# untitled.net
KiCad netlist of a schematic drawn in EAGLE
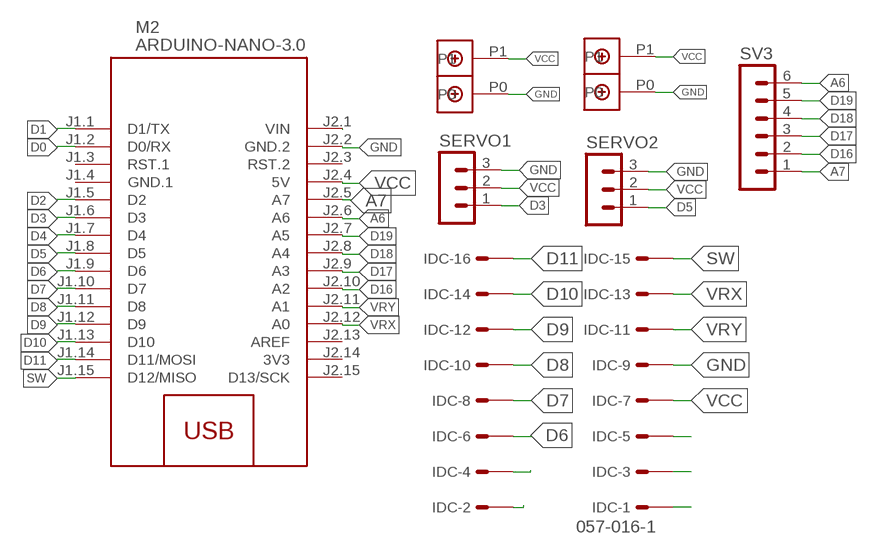
[diagram p0: schematic, sheet 1]

(export (version "E")
  (design (tool "Eeschema 10.0.6"))
  (components
    (comp (ref "IDC")
      (value "057-016-1")
      (footprint "eagle-import:057-016-1")
      (libsource (lib "eagle-import") (part "057-016-1"))
    )
    (comp (ref "M2")
      (value "ARDUINO-NANO-3.0")
      (footprint "eagle-import:ARDUINO-NANO-3.0")
      (libsource (lib "eagle-import") (part "ARDUINO-NANO-3.0"))
    )
    (comp (ref "SERVO1")
      (value "MA03-1")
      (footprint "eagle-import:MA03-1")
      (libsource (lib "eagle-import") (part "MA03-1"))
    )
    (comp (ref "SERVO2")
      (value "MA03-1")
      (footprint "eagle-import:MA03-1")
      (libsource (lib "eagle-import") (part "MA03-1"))
    )
    (comp (ref "SV3")
      (value "MA06-1")
      (footprint "eagle-import:MA06-1")
      (libsource (lib "eagle-import") (part "MA06-1"))
    )
    (comp (ref "U$1")
      (value "DBCONN-1X2")
      (footprint "eagle-import:DBCONN-1X2")
      (libsource (lib "eagle-import") (part "DBCONN-1X2"))
    )
    (comp (ref "U$2")
      (value "DBCONN-1X2")
      (footprint "eagle-import:DBCONN-1X2")
      (libsource (lib "eagle-import") (part "DBCONN-1X2"))
    )
  )
  (nets
    (net (code "1") (name "/3V3") (class "Default")
      (node (ref "M2") (pin "J2.14") (pinfunction "3V3_J2.14") (pintype "power_in"))
    )
    (net (code "2") (name "/D") (class "Default")
      (node (ref "IDC") (pin "2") (pinfunction "S_2") (pintype "passive"))
      (node (ref "IDC") (pin "4") (pinfunction "S_4") (pintype "passive"))
    )
    (net (code "3") (name "/GND.1") (class "Default")
      (node (ref "M2") (pin "J1.4") (pinfunction "GND.1_J1.4") (pintype "power_in"))
    )
    (net (code "4") (name "A6") (class "Default")
      (node (ref "M2") (pin "J2.6") (pinfunction "A6_J2.6") (pintype "bidirectional"))
      (node (ref "SV3") (pin "6") (pinfunction "6_6") (pintype "passive"))
    )
    (net (code "5") (name "A7") (class "Default")
      (node (ref "M2") (pin "J2.5") (pinfunction "A7_J2.5") (pintype "bidirectional"))
      (node (ref "SV3") (pin "1") (pinfunction "1_1") (pintype "passive"))
    )
    (net (code "6") (name "D0") (class "Default")
      (node (ref "M2") (pin "J1.2") (pinfunction "D0/RX_J1.2") (pintype "bidirectional"))
    )
    (net (code "7") (name "D1") (class "Default")
      (node (ref "M2") (pin "J1.1") (pinfunction "D1/TX_J1.1") (pintype "bidirectional"))
    )
    (net (code "8") (name "D2") (class "Default")
      (node (ref "M2") (pin "J1.5") (pinfunction "D2_J1.5") (pintype "bidirectional"))
    )
    (net (code "9") (name "D3") (class "Default")
      (node (ref "M2") (pin "J1.6") (pinfunction "D3_J1.6") (pintype "bidirectional"))
      (node (ref "SERVO1") (pin "1") (pinfunction "1_1") (pintype "passive"))
    )
    (net (code "10") (name "D4") (class "Default")
      (node (ref "M2") (pin "J1.7") (pinfunction "D4_J1.7") (pintype "bidirectional"))
    )
    (net (code "11") (name "D5") (class "Default")
      (node (ref "M2") (pin "J1.8") (pinfunction "D5_J1.8") (pintype "bidirectional"))
      (node (ref "SERVO2") (pin "1") (pinfunction "1_1") (pintype "passive"))
    )
    (net (code "12") (name "D6") (class "Default")
      (node (ref "IDC") (pin "6") (pinfunction "S_6") (pintype "passive"))
      (node (ref "M2") (pin "J1.9") (pinfunction "D6_J1.9") (pintype "bidirectional"))
    )
    (net (code "13") (name "D7") (class "Default")
      (node (ref "IDC") (pin "8") (pinfunction "S_8") (pintype "passive"))
      (node (ref "M2") (pin "J1.10") (pinfunction "D7_J1.10") (pintype "bidirectional"))
    )
    (net (code "14") (name "D8") (class "Default")
      (node (ref "IDC") (pin "10") (pinfunction "S_10") (pintype "passive"))
      (node (ref "M2") (pin "J1.11") (pinfunction "D8_J1.11") (pintype "bidirectional"))
    )
    (net (code "15") (name "D9") (class "Default")
      (node (ref "IDC") (pin "12") (pinfunction "S_12") (pintype "passive"))
      (node (ref "M2") (pin "J1.12") (pinfunction "D9_J1.12") (pintype "bidirectional"))
    )
    (net (code "16") (name "D10") (class "Default")
      (node (ref "IDC") (pin "14") (pinfunction "S_14") (pintype "passive"))
      (node (ref "M2") (pin "J1.13") (pinfunction "D10_J1.13") (pintype "bidirectional"))
    )
    (net (code "17") (name "D11") (class "Default")
      (node (ref "IDC") (pin "16") (pinfunction "S_16") (pintype "passive"))
      (node (ref "M2") (pin "J1.14") (pinfunction "D11/MOSI_J1.14") (pintype "bidirectional"))
    )
    (net (code "18") (name "D16") (class "Default")
      (node (ref "M2") (pin "J2.10") (pinfunction "A2_J2.10") (pintype "bidirectional"))
      (node (ref "SV3") (pin "2") (pinfunction "2_2") (pintype "passive"))
    )
    (net (code "19") (name "D17") (class "Default")
      (node (ref "M2") (pin "J2.9") (pinfunction "A3_J2.9") (pintype "bidirectional"))
      (node (ref "SV3") (pin "3") (pinfunction "3_3") (pintype "passive"))
    )
    (net (code "20") (name "D18") (class "Default")
      (node (ref "M2") (pin "J2.8") (pinfunction "A4_J2.8") (pintype "bidirectional"))
      (node (ref "SV3") (pin "4") (pinfunction "4_4") (pintype "passive"))
    )
    (net (code "21") (name "D19") (class "Default")
      (node (ref "M2") (pin "J2.7") (pinfunction "A5_J2.7") (pintype "bidirectional"))
      (node (ref "SV3") (pin "5") (pinfunction "5_5") (pintype "passive"))
    )
    (net (code "22") (name "GND") (class "Default")
      (node (ref "IDC") (pin "9") (pinfunction "S_9") (pintype "passive"))
      (node (ref "M2") (pin "J2.2") (pinfunction "GND.2_J2.2") (pintype "power_in"))
      (node (ref "SERVO1") (pin "3") (pinfunction "3_3") (pintype "passive"))
      (node (ref "SERVO2") (pin "3") (pinfunction "3_3") (pintype "passive"))
      (node (ref "U$1") (pin "P0") (pinfunction "P0_P0") (pintype "bidirectional"))
      (node (ref "U$2") (pin "P0") (pinfunction "P0_P0") (pintype "bidirectional"))
    )
    (net (code "23") (name "SW") (class "Default")
      (node (ref "IDC") (pin "15") (pinfunction "S_15") (pintype "passive"))
      (node (ref "M2") (pin "J1.15") (pinfunction "D12/MISO_J1.15") (pintype "bidirectional"))
    )
    (net (code "24") (name "VCC") (class "Default")
      (node (ref "IDC") (pin "7") (pinfunction "S_7") (pintype "passive"))
      (node (ref "M2") (pin "J2.1") (pinfunction "VIN_J2.1") (pintype "power_in"))
      (node (ref "M2") (pin "J2.4") (pinfunction "5V_J2.4") (pintype "power_in"))
      (node (ref "SERVO1") (pin "2") (pinfunction "2_2") (pintype "passive"))
      (node (ref "SERVO2") (pin "2") (pinfunction "2_2") (pintype "passive"))
      (node (ref "U$1") (pin "P1") (pinfunction "P1_P1") (pintype "bidirectional"))
      (node (ref "U$2") (pin "P1") (pinfunction "P1_P1") (pintype "bidirectional"))
    )
    (net (code "25") (name "VRX") (class "Default")
      (node (ref "IDC") (pin "13") (pinfunction "S_13") (pintype "passive"))
      (node (ref "M2") (pin "J2.12") (pinfunction "A0_J2.12") (pintype "bidirectional"))
    )
    (net (code "26") (name "VRY") (class "Default")
      (node (ref "IDC") (pin "11") (pinfunction "S_11") (pintype "passive"))
      (node (ref "M2") (pin "J2.11") (pinfunction "A1_J2.11") (pintype "bidirectional"))
    )
    (net (code "27") (name "unconnected-(IDCA-S-Pad1)") (class "Default")
      (node (ref "IDC") (pin "1") (pinfunction "S_1") (pintype "passive"))
    )
    (net (code "28") (name "unconnected-(IDCJ-S-Pad3)") (class "Default")
      (node (ref "IDC") (pin "3") (pinfunction "S_3") (pintype "passive"))
    )
    (net (code "29") (name "unconnected-(IDCL-S-Pad5)") (class "Default")
      (node (ref "IDC") (pin "5") (pinfunction "S_5") (pintype "passive"))
    )
    (net (code "30") (name "unconnected-(M2-AREF-PadJ2.13)") (class "Default")
      (node (ref "M2") (pin "J2.13") (pinfunction "AREF_J2.13") (pintype "bidirectional"))
    )
    (net (code "31") (name "unconnected-(M2-D13{slash}SCK-PadJ2.15)") (class "Default")
      (node (ref "M2") (pin "J2.15") (pinfunction "D13/SCK_J2.15") (pintype "bidirectional"))
    )
    (net (code "32") (name "unconnected-(M2-RST.1-PadJ1.3)") (class "Default")
      (node (ref "M2") (pin "J1.3") (pinfunction "RST.1_J1.3") (pintype "bidirectional"))
    )
    (net (code "33") (name "unconnected-(M2-RST.2-PadJ2.3)") (class "Default")
      (node (ref "M2") (pin "J2.3") (pinfunction "RST.2_J2.3") (pintype "bidirectional"))
    )
  )
)
